# channel_45678.net
KiCad netlist of a schematic drawn in Altium Designer
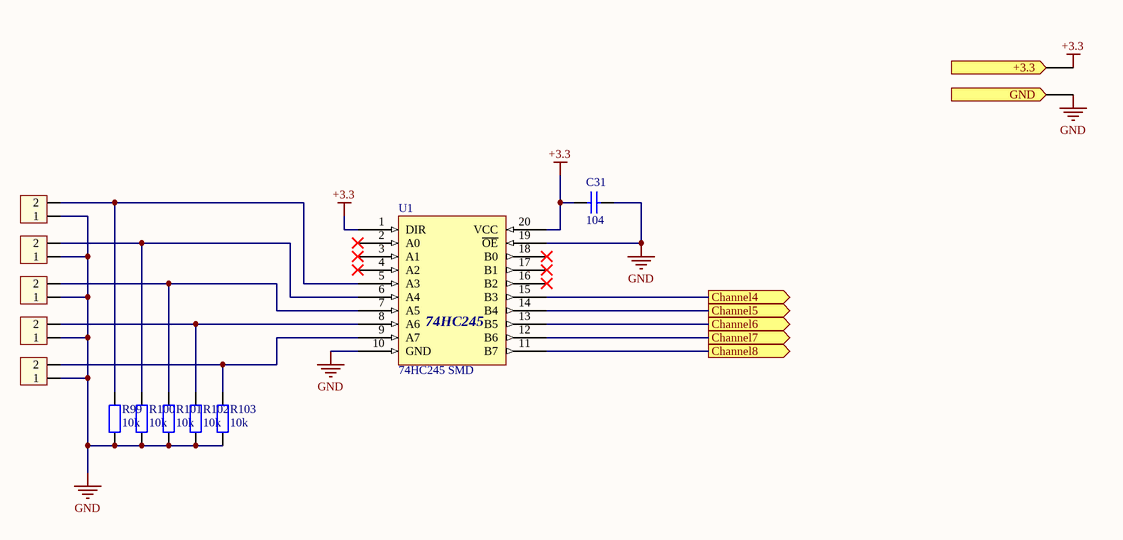
[diagram p0: channel_45678.SchDoc]

(export (version "E")
  (design (tool "Eeschema 10.0.6"))
  (components
    (comp (ref "C31")
      (value "104")
      (footprint "tu 0603")
      (description "Dán")
      (libsource (lib "TrungVan_Lib") (part "Tu 0603 104 50V 10%"))
    )
    (comp (ref "H4")
      (value "Header 2P 2.54 Duc Thang")
      (footprint "15EDGR-3.81-2P")
      (description "Cắm")
      (libsource (lib "TrungVan_Lib") (part "Header 2P 2.54 Duc Thang"))
    )
    (comp (ref "H5")
      (value "Header 2P 2.54 Duc Thang")
      (footprint "15EDGR-3.81-2P")
      (description "Cắm")
      (libsource (lib "TrungVan_Lib") (part "Header 2P 2.54 Duc Thang"))
    )
    (comp (ref "H6")
      (value "Header 2P 2.54 Duc Thang")
      (footprint "15EDGR-3.81-2P")
      (description "Cắm")
      (libsource (lib "TrungVan_Lib") (part "Header 2P 2.54 Duc Thang"))
    )
    (comp (ref "H7")
      (value "Header 2P 2.54 Duc Thang")
      (footprint "15EDGR-3.81-2P")
      (description "Cắm")
      (libsource (lib "TrungVan_Lib") (part "Header 2P 2.54 Duc Thang"))
    )
    (comp (ref "H8")
      (value "Header 2P 2.54 Duc Thang")
      (footprint "15EDGR-3.81-2P")
      (description "Cắm")
      (libsource (lib "TrungVan_Lib") (part "Header 2P 2.54 Duc Thang"))
    )
    (comp (ref "R99")
      (value "10k")
      (footprint "tro smd 0603")
      (description "Dán")
      (libsource (lib "TrungVan_Lib") (part "Tro 0603 1% 10k"))
    )
    (comp (ref "R100")
      (value "10k")
      (footprint "tro smd 0603")
      (description "Dán")
      (libsource (lib "TrungVan_Lib") (part "Tro 0603 1% 10k"))
    )
    (comp (ref "R101")
      (value "10k")
      (footprint "tro smd 0603")
      (description "Dán")
      (libsource (lib "TrungVan_Lib") (part "Tro 0603 1% 10k"))
    )
    (comp (ref "R102")
      (value "10k")
      (footprint "tro smd 0603")
      (description "Dán")
      (libsource (lib "TrungVan_Lib") (part "Tro 0603 1% 10k"))
    )
    (comp (ref "R103")
      (value "10k")
      (footprint "tro smd 0603")
      (description "Dán")
      (libsource (lib "TrungVan_Lib") (part "Tro 0603 1% 10k"))
    )
    (comp (ref "U1")
      (value "74HC245 SMD")
      (footprint "SOP 20")
      (description "Dán")
      (libsource (lib "TrungVan_Lib") (part "74HC245 SMD"))
    )
  )
  (nets
    (net (code "1") (name "+3.3") (class "Default")
      (node (ref "C31") (pin "2") (pinfunction "2_2") (pintype "passive"))
      (node (ref "U1") (pin "1") (pinfunction "DIR_1") (pintype "input"))
      (node (ref "U1") (pin "20") (pinfunction "VCC_20") (pintype "input"))
    )
    (net (code "2") (name "/Channel4") (class "Default")
      (node (ref "U1") (pin "15") (pinfunction "B3_15") (pintype "output"))
    )
    (net (code "3") (name "/Channel5") (class "Default")
      (node (ref "U1") (pin "14") (pinfunction "B4_14") (pintype "output"))
    )
    (net (code "4") (name "/Channel6") (class "Default")
      (node (ref "U1") (pin "13") (pinfunction "B5_13") (pintype "output"))
    )
    (net (code "5") (name "/Channel7") (class "Default")
      (node (ref "U1") (pin "12") (pinfunction "B6_12") (pintype "output"))
    )
    (net (code "6") (name "/Channel8") (class "Default")
      (node (ref "U1") (pin "11") (pinfunction "B7_11") (pintype "output"))
    )
    (net (code "7") (name "GND") (class "Default")
      (node (ref "C31") (pin "1") (pinfunction "1_1") (pintype "passive"))
      (node (ref "H4") (pin "1") (pinfunction "1_1") (pintype "passive"))
      (node (ref "H5") (pin "1") (pinfunction "1_1") (pintype "passive"))
      (node (ref "H6") (pin "1") (pinfunction "1_1") (pintype "passive"))
      (node (ref "H7") (pin "1") (pinfunction "1_1") (pintype "passive"))
      (node (ref "H8") (pin "1") (pinfunction "1_1") (pintype "passive"))
      (node (ref "R100") (pin "1") (pinfunction "1_1") (pintype "passive"))
      (node (ref "R101") (pin "1") (pinfunction "1_1") (pintype "passive"))
      (node (ref "R102") (pin "1") (pinfunction "1_1") (pintype "passive"))
      (node (ref "R103") (pin "1") (pinfunction "1_1") (pintype "passive"))
      (node (ref "R99") (pin "1") (pinfunction "1_1") (pintype "passive"))
      (node (ref "U1") (pin "10") (pinfunction "GND_10") (pintype "input"))
      (node (ref "U1") (pin "19") (pinfunction "~{OE}_19") (pintype "input"))
    )
    (net (code "8") (name "Net-(U1-A3)") (class "Default")
      (node (ref "H4") (pin "2") (pinfunction "2_2") (pintype "passive"))
      (node (ref "R99") (pin "2") (pinfunction "2_2") (pintype "passive"))
      (node (ref "U1") (pin "5") (pinfunction "A3_5") (pintype "input"))
    )
    (net (code "9") (name "Net-(U1-A4)") (class "Default")
      (node (ref "H5") (pin "2") (pinfunction "2_2") (pintype "passive"))
      (node (ref "R100") (pin "2") (pinfunction "2_2") (pintype "passive"))
      (node (ref "U1") (pin "6") (pinfunction "A4_6") (pintype "input"))
    )
    (net (code "10") (name "Net-(U1-A5)") (class "Default")
      (node (ref "H6") (pin "2") (pinfunction "2_2") (pintype "passive"))
      (node (ref "R101") (pin "2") (pinfunction "2_2") (pintype "passive"))
      (node (ref "U1") (pin "7") (pinfunction "A5_7") (pintype "input"))
    )
    (net (code "11") (name "Net-(U1-A6)") (class "Default")
      (node (ref "H7") (pin "2") (pinfunction "2_2") (pintype "passive"))
      (node (ref "R102") (pin "2") (pinfunction "2_2") (pintype "passive"))
      (node (ref "U1") (pin "8") (pinfunction "A6_8") (pintype "input"))
    )
    (net (code "12") (name "Net-(U1-A7)") (class "Default")
      (node (ref "H8") (pin "2") (pinfunction "2_2") (pintype "passive"))
      (node (ref "R103") (pin "2") (pinfunction "2_2") (pintype "passive"))
      (node (ref "U1") (pin "9") (pinfunction "A7_9") (pintype "input"))
    )
    (net (code "13") (name "unconnected-(U1-A0-Pad2)") (class "Default")
      (node (ref "U1") (pin "2") (pinfunction "A0_2") (pintype "input+no_connect"))
    )
    (net (code "14") (name "unconnected-(U1-A1-Pad3)") (class "Default")
      (node (ref "U1") (pin "3") (pinfunction "A1_3") (pintype "input+no_connect"))
    )
    (net (code "15") (name "unconnected-(U1-A2-Pad4)") (class "Default")
      (node (ref "U1") (pin "4") (pinfunction "A2_4") (pintype "input+no_connect"))
    )
    (net (code "16") (name "unconnected-(U1-B0-Pad18)") (class "Default")
      (node (ref "U1") (pin "18") (pinfunction "B0_18") (pintype "output+no_connect"))
    )
    (net (code "17") (name "unconnected-(U1-B1-Pad17)") (class "Default")
      (node (ref "U1") (pin "17") (pinfunction "B1_17") (pintype "output+no_connect"))
    )
    (net (code "18") (name "unconnected-(U1-B2-Pad16)") (class "Default")
      (node (ref "U1") (pin "16") (pinfunction "B2_16") (pintype "output+no_connect"))
    )
  )
)
